# untitled_upd.net
KiCad netlist of a schematic drawn in EAGLE
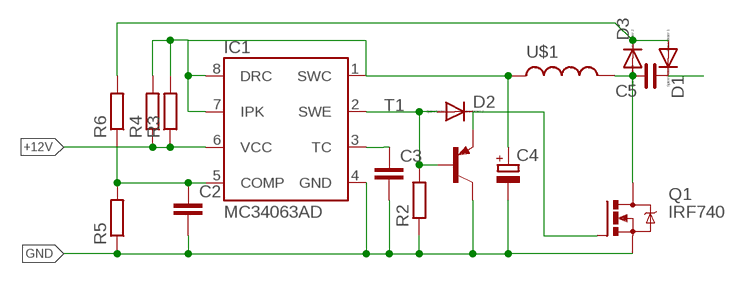
[diagram p0: schematic, sheet 1]

(export (version "E")
  (design (tool "Eeschema 10.0.6"))
  (components
    (comp (ref "C2")
      (value "C-EUC0805K")
      (footprint "eagle-import:C0805K")
      (libsource (lib "eagle-import") (part "C-EUC0805K"))
    )
    (comp (ref "C3")
      (value "C-EUC0805K")
      (footprint "eagle-import:C0805K")
      (libsource (lib "eagle-import") (part "C-EUC0805K"))
    )
    (comp (ref "C4")
      (value "CPOL-EU153CLV-0605")
      (footprint "eagle-import:153CLV-0605")
      (libsource (lib "eagle-import") (part "CPOL-EU153CLV-0605"))
    )
    (comp (ref "C5")
      (value "C_0805")
      (footprint "eagle-import:C0805")
      (libsource (lib "eagle-import") (part "C_0805"))
    )
    (comp (ref "D1")
      (value "DIODE-DO-214AC")
      (footprint "eagle-import:DO-214AC")
      (libsource (lib "eagle-import") (part "DIODE-DO-214AC"))
    )
    (comp (ref "D2")
      (value "DIODE-DO-214AC")
      (footprint "eagle-import:DO-214AC")
      (libsource (lib "eagle-import") (part "DIODE-DO-214AC"))
    )
    (comp (ref "D3")
      (value "DIODE-DO-214AC")
      (footprint "eagle-import:DO-214AC")
      (libsource (lib "eagle-import") (part "DIODE-DO-214AC"))
    )
    (comp (ref "IC1")
      (value "MC34063AD")
      (footprint "eagle-import:SO08")
      (libsource (lib "eagle-import") (part "MC34063AD"))
    )
    (comp (ref "Q1")
      (value "IRF740")
      (footprint "eagle-import:TO220BV")
      (libsource (lib "eagle-import") (part "IRF740"))
    )
    (comp (ref "R2")
      (value "R-EU_M0805")
      (footprint "eagle-import:M0805")
      (libsource (lib "eagle-import") (part "R-EU_M0805"))
    )
    (comp (ref "R3")
      (value "R-EU_M0805")
      (footprint "eagle-import:M0805")
      (libsource (lib "eagle-import") (part "R-EU_M0805"))
    )
    (comp (ref "R4")
      (value "R-EU_M0805")
      (footprint "eagle-import:M0805")
      (libsource (lib "eagle-import") (part "R-EU_M0805"))
    )
    (comp (ref "R5")
      (value "R-EU_M0805")
      (footprint "eagle-import:M0805")
      (libsource (lib "eagle-import") (part "R-EU_M0805"))
    )
    (comp (ref "R6")
      (value "R-EU_M0805")
      (footprint "eagle-import:M0805")
      (libsource (lib "eagle-import") (part "R-EU_M0805"))
    )
    (comp (ref "T1")
      (value "BC807-16-PNP-SOT23-BEC")
      (footprint "eagle-import:SOT23-BEC")
      (libsource (lib "eagle-import") (part "-PNP-SOT23-BECBC807-16"))
    )
    (comp (ref "U$1")
      (value "MSS1260")
      (footprint "eagle-import:MSS1260")
      (libsource (lib "eagle-import") (part "MSS1260"))
    )
  )
  (nets
    (net (code "1") (name "+12V") (class "Default")
      (node (ref "IC1") (pin "6") (pinfunction "VCC_6") (pintype "power_in"))
      (node (ref "R3") (pin "1") (pinfunction "1_1") (pintype "passive"))
      (node (ref "R4") (pin "1") (pinfunction "1_1") (pintype "passive"))
    )
    (net (code "2") (name "GND") (class "Default")
      (node (ref "C2") (pin "2") (pinfunction "2_2") (pintype "passive"))
      (node (ref "C3") (pin "2") (pinfunction "2_2") (pintype "passive"))
      (node (ref "C4") (pin "-") (pinfunction "-_-") (pintype "passive"))
      (node (ref "IC1") (pin "4") (pinfunction "GND_4") (pintype "power_in"))
      (node (ref "Q1") (pin "S") (pinfunction "S_S") (pintype "passive"))
      (node (ref "R2") (pin "1") (pinfunction "1_1") (pintype "passive"))
      (node (ref "R5") (pin "1") (pinfunction "1_1") (pintype "passive"))
      (node (ref "T1") (pin "C") (pinfunction "C_C") (pintype "passive"))
    )
    (net (code "3") (name "Net-(C5-Pad1)") (class "Default")
      (node (ref "C5") (pin "1") (pinfunction "1_1") (pintype "passive"))
      (node (ref "D1") (pin "C") (pinfunction "C_C") (pintype "passive"))
    )
    (net (code "4") (name "Net-(C5-Pad2)") (class "Default")
      (node (ref "C5") (pin "2") (pinfunction "2_2") (pintype "passive"))
      (node (ref "D3") (pin "A") (pinfunction "A_A") (pintype "passive"))
      (node (ref "Q1") (pin "D") (pinfunction "D_D") (pintype "passive"))
      (node (ref "U$1") (pin "P$1") (pinfunction "P$1_P$1") (pintype "passive"))
    )
    (net (code "5") (name "Net-(D1-PadA)") (class "Default")
      (node (ref "D1") (pin "A") (pinfunction "A_A") (pintype "passive"))
      (node (ref "D3") (pin "C") (pinfunction "C_C") (pintype "passive"))
      (node (ref "R6") (pin "2") (pinfunction "2_2") (pintype "passive"))
    )
    (net (code "6") (name "Net-(D2-PadC)") (class "Default")
      (node (ref "D2") (pin "C") (pinfunction "C_C") (pintype "passive"))
      (node (ref "Q1") (pin "G") (pinfunction "G_G") (pintype "passive"))
      (node (ref "T1") (pin "E") (pinfunction "E_E") (pintype "passive"))
    )
    (net (code "7") (name "Net-(IC1-COMP)") (class "Default")
      (node (ref "C2") (pin "1") (pinfunction "1_1") (pintype "passive"))
      (node (ref "IC1") (pin "5") (pinfunction "COMP_5") (pintype "input"))
      (node (ref "R5") (pin "2") (pinfunction "2_2") (pintype "passive"))
      (node (ref "R6") (pin "1") (pinfunction "1_1") (pintype "passive"))
    )
    (net (code "8") (name "Net-(IC1-DRC)") (class "Default")
      (node (ref "C4") (pin "+") (pinfunction "+_+") (pintype "passive"))
      (node (ref "IC1") (pin "1") (pinfunction "SWC_1") (pintype "bidirectional"))
      (node (ref "IC1") (pin "7") (pinfunction "IPK_7") (pintype "input"))
      (node (ref "IC1") (pin "8") (pinfunction "DRC_8") (pintype "input"))
      (node (ref "R3") (pin "2") (pinfunction "2_2") (pintype "passive"))
      (node (ref "R4") (pin "2") (pinfunction "2_2") (pintype "passive"))
      (node (ref "U$1") (pin "P$2") (pinfunction "P$2_P$2") (pintype "passive"))
    )
    (net (code "9") (name "Net-(IC1-SWE)") (class "Default")
      (node (ref "D2") (pin "A") (pinfunction "A_A") (pintype "passive"))
      (node (ref "IC1") (pin "2") (pinfunction "SWE_2") (pintype "bidirectional"))
      (node (ref "R2") (pin "2") (pinfunction "2_2") (pintype "passive"))
      (node (ref "T1") (pin "B") (pinfunction "B_B") (pintype "passive"))
    )
    (net (code "10") (name "Net-(IC1-TC)") (class "Default")
      (node (ref "C3") (pin "1") (pinfunction "1_1") (pintype "passive"))
      (node (ref "IC1") (pin "3") (pinfunction "TC_3") (pintype "passive"))
    )
  )
)
